# FMC_CONNECTOR.net
KiCad netlist of a schematic drawn in Altium Designer
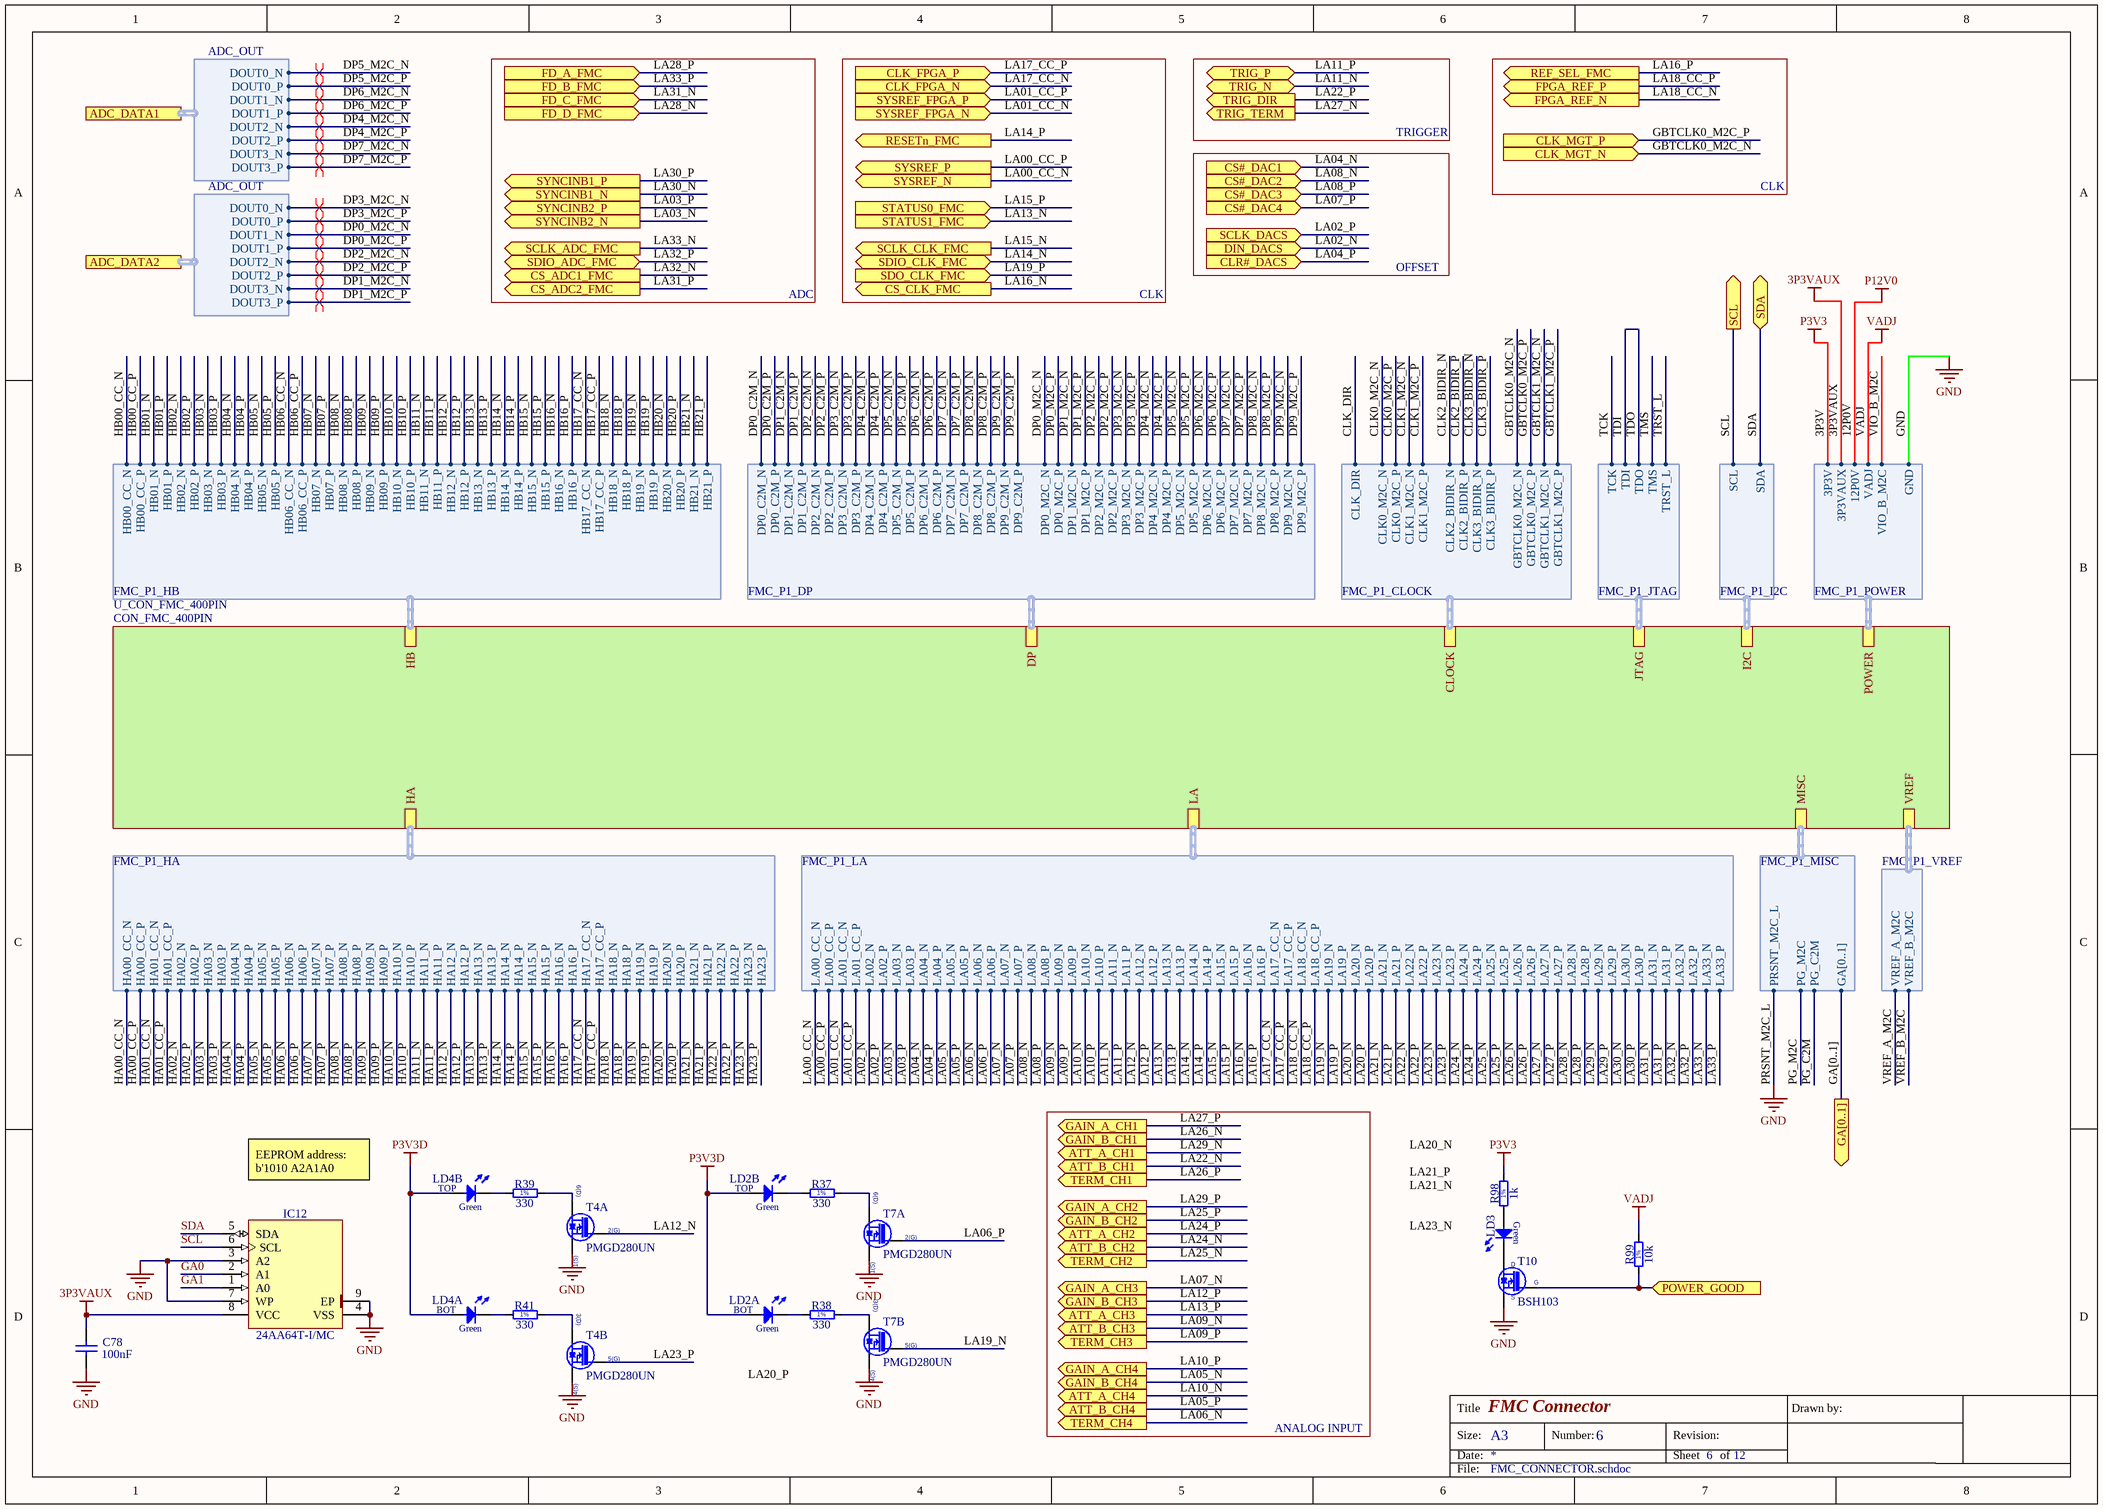
[diagram p0: FMC_CONNECTOR.schdoc]

(export (version "E")
  (design (tool "Eeschema 10.0.6"))
  (components
    (comp (ref "C78")
      (value "100nF")
      (footprint "CAPC0603X33N")
      (description "Non-polarised capacitor")
      (fields
        (field (name "TOLERANCE") "±10%")
        (field (name "PART NUMBER") "CC0201_100NF_6.3V_10%_X5R")
        (field (name "AUTHOR") "CERN DEM JLC")
      )
      (libsource (lib "Capacitors") (part "Capacitor - non polarized"))
    )
    (comp (ref "IC12")
      (value "24AA64T-I/MC")
      (footprint "SON50P300X200X100-9N-R175X155")
      (description "1.7V-5.5V 64K I2C Serial EEPROM")
      (fields (field (name "MANUFACTURER") "MICROCHIP TECHNOLOGY") (field (name "AUTHOR") "CERN DEM JLC"))
      (libsource (lib "ICs And Semiconductors") (part "24AA64T-I/MC"))
    )
    (comp (ref "LD2")
      (value "~")
      (footprint "553-xxxx-300")
      (description "LED x2 Green 553-0122-300")
      (fields
        (field (name "MANUFACTURER PART NUMBER") "553-0122-300")
        (field (name "MANUFACTURER") "Dialight")
      )
      (libsource (lib "FMC_ADC") (part "LED x2 Green 553-0122-300"))
    )
    (comp (ref "LD3")
      (value "~")
      (footprint "LED0603X65N")
      (description "LED Green, SMD 0603")
      (fields
        (field (name "MANUFACTURER PART NUMBER") "KPH-1608CGCK")
        (field (name "MANUFACTURER") "Kingbright")
      )
      (libsource (lib "FMC_ADC") (part "KPH-1608CGCK"))
    )
    (comp (ref "LD4")
      (value "~")
      (footprint "553-xxxx-300")
      (description "LED x2 Green 553-0122-300")
      (fields
        (field (name "MANUFACTURER PART NUMBER") "553-0122-300")
        (field (name "MANUFACTURER") "Dialight")
      )
      (libsource (lib "FMC_ADC") (part "LED x2 Green 553-0122-300"))
    )
    (comp (ref "R37")
      (value "330")
      (footprint "RESC1005X40N")
      (description "Resistor - 1%")
      (fields
        (field (name "PART NUMBER") "R0402_330R_1%_0.0625W_100PPM")
        (field (name "POWER") "0.0625W")
        (field (name "AUTHOR") "CERN DEM JLC")
      )
      (libsource (lib "Resistors") (part "Resistor - 1%"))
    )
    (comp (ref "R38")
      (value "330")
      (footprint "RESC1005X40N")
      (description "Resistor - 1%")
      (fields
        (field (name "PART NUMBER") "R0402_330R_1%_0.0625W_100PPM")
        (field (name "POWER") "0.0625W")
        (field (name "AUTHOR") "CERN DEM JLC")
      )
      (libsource (lib "Resistors") (part "Resistor - 1%"))
    )
    (comp (ref "R39")
      (value "330")
      (footprint "RESC1005X40N")
      (description "Resistor - 1%")
      (fields
        (field (name "PART NUMBER") "R0402_330R_1%_0.0625W_100PPM")
        (field (name "POWER") "0.0625W")
        (field (name "AUTHOR") "CERN DEM JLC")
      )
      (libsource (lib "Resistors") (part "Resistor - 1%"))
    )
    (comp (ref "R41")
      (value "330")
      (footprint "RESC1005X40N")
      (description "Resistor - 1%")
      (fields
        (field (name "PART NUMBER") "R0402_330R_1%_0.0625W_100PPM")
        (field (name "POWER") "0.0625W")
        (field (name "AUTHOR") "CERN DEM JLC")
      )
      (libsource (lib "Resistors") (part "Resistor - 1%"))
    )
    (comp (ref "R98")
      (value "1k")
      (footprint "RESC1005X40N")
      (description "Resistor - 1%")
      (fields
        (field (name "PART NUMBER") "R0402_1K_1%_0.0625W_100PPM")
        (field (name "POWER") "0.0625W")
        (field (name "AUTHOR") "CERN DEM JLC")
      )
      (libsource (lib "Resistors") (part "Resistor - 1%"))
    )
    (comp (ref "R99")
      (value "10k")
      (footprint "RESC1608X55N")
      (description "Resistor - 1%")
      (fields
        (field (name "PART NUMBER") "R0603_10K_1%_0.1W_100PPM")
        (field (name "POWER") "0.1W")
        (field (name "AUTHOR") "CERN DEM JLC")
      )
      (libsource (lib "Resistors") (part "Resistor - 1%"))
    )
    (comp (ref "T4")
      (value "PMGD280UN")
      (footprint "SOT65P210X110-6N")
      (description "Dual N-Channel micro TrenchMOS™ Ultra Low Level FET")
      (fields (field (name "MANUFACTURER") "NXP SEMICONDUCTORS") (field (name "AUTHOR") "CERN DEM JLC"))
      (libsource (lib "ICs And Semiconductors") (part "PMGD280UN"))
    )
    (comp (ref "T7")
      (value "PMGD280UN")
      (footprint "SOT65P210X110-6N")
      (description "Dual N-Channel micro TrenchMOS™ Ultra Low Level FET")
      (fields (field (name "MANUFACTURER") "NXP SEMICONDUCTORS") (field (name "AUTHOR") "CERN DEM JLC"))
      (libsource (lib "ICs And Semiconductors") (part "PMGD280UN"))
    )
    (comp (ref "T10")
      (value "BSH103")
      (footprint "SOT95P230X110-3N")
      (description "N-CHANNEL MOSFET WITH DIODE")
      (fields (field (name "MANUFACTURER") "NEXPERIA") (field (name "AUTHOR") "CERN DEM JLC"))
      (libsource (lib "ICs And Semiconductors") (part "N-MOSFET-D 1G 2S 3D"))
    )
  )
  (nets
    (net (code "61") (name "/GA0") (class "Default")
      (node (ref "IC12") (pin "2") (pinfunction "A1_2") (pintype "input"))
    )
    (net (code "62") (name "/GA1") (class "Default")
      (node (ref "IC12") (pin "1") (pinfunction "A0_1") (pintype "input"))
    )
    (net (code "173") (name "/LA06_P") (class "Default")
      (node (ref "T7") (pin "2") (pinfunction "G_2") (pintype "passive"))
    )
    (net (code "184") (name "/LA12_N") (class "Default")
      (node (ref "T4") (pin "2") (pinfunction "G_2") (pintype "passive"))
    )
    (net (code "198") (name "/LA19_N") (class "Default")
      (node (ref "T7") (pin "5") (pinfunction "G_5") (pintype "passive"))
    )
    (net (code "207") (name "/LA23_P") (class "Default")
      (node (ref "T4") (pin "5") (pinfunction "G_5") (pintype "passive"))
    )
    (net (code "230") (name "/POWER_GOOD") (class "Default")
      (node (ref "R99") (pin "1") (pinfunction "1_1") (pintype "passive"))
      (node (ref "T10") (pin "1") (pinfunction "G_1") (pintype "passive"))
    )
    (net (code "231") (name "/SCL") (class "Default")
      (node (ref "IC12") (pin "6") (pinfunction "SCL_6") (pintype "input"))
    )
    (net (code "232") (name "/SDA") (class "Default")
      (node (ref "IC12") (pin "5") (pinfunction "SDA_5") (pintype "bidirectional"))
    )
    (net (code "251") (name "3P3VAUX") (class "Default")
      (node (ref "C78") (pin "2") (pinfunction "2_2") (pintype "passive"))
      (node (ref "IC12") (pin "8") (pinfunction "VCC_8") (pintype "power_in"))
    )
    (net (code "252") (name "GND") (class "Default")
      (node (ref "C78") (pin "1") (pinfunction "1_1") (pintype "passive"))
      (node (ref "IC12") (pin "3") (pinfunction "A2_3") (pintype "input"))
      (node (ref "IC12") (pin "4") (pinfunction "VSS_4") (pintype "power_in"))
      (node (ref "IC12") (pin "7") (pinfunction "WP_7") (pintype "input"))
      (node (ref "IC12") (pin "9") (pinfunction "EP_9") (pintype "power_in"))
      (node (ref "T10") (pin "2") (pinfunction "S_2") (pintype "passive"))
      (node (ref "T4") (pin "1") (pinfunction "S_1") (pintype "passive"))
      (node (ref "T4") (pin "4") (pinfunction "S_4") (pintype "passive"))
      (node (ref "T7") (pin "1") (pinfunction "S_1") (pintype "passive"))
      (node (ref "T7") (pin "4") (pinfunction "S_4") (pintype "passive"))
    )
    (net (code "253") (name "Net-(LD2A-C)") (class "Default")
      (node (ref "LD2") (pin "1") (pinfunction "C_1") (pintype "passive"))
      (node (ref "R38") (pin "1") (pinfunction "1_1") (pintype "passive"))
    )
    (net (code "254") (name "Net-(LD2B-C)") (class "Default")
      (node (ref "LD2") (pin "3") (pinfunction "C_3") (pintype "passive"))
      (node (ref "R37") (pin "1") (pinfunction "1_1") (pintype "passive"))
    )
    (net (code "255") (name "Net-(LD3-A)") (class "Default")
      (node (ref "LD3") (pin "1") (pinfunction "A_1") (pintype "passive"))
      (node (ref "R98") (pin "1") (pinfunction "1_1") (pintype "passive"))
    )
    (net (code "256") (name "Net-(LD3-C)") (class "Default")
      (node (ref "LD3") (pin "2") (pinfunction "C_2") (pintype "passive"))
      (node (ref "T10") (pin "3") (pinfunction "D_3") (pintype "passive"))
    )
    (net (code "257") (name "Net-(LD4A-C)") (class "Default")
      (node (ref "LD4") (pin "1") (pinfunction "C_1") (pintype "passive"))
      (node (ref "R41") (pin "1") (pinfunction "1_1") (pintype "passive"))
    )
    (net (code "258") (name "Net-(LD4B-C)") (class "Default")
      (node (ref "LD4") (pin "3") (pinfunction "C_3") (pintype "passive"))
      (node (ref "R39") (pin "1") (pinfunction "1_1") (pintype "passive"))
    )
    (net (code "259") (name "Net-(T4A-D)") (class "Default")
      (node (ref "R39") (pin "2") (pinfunction "2_2") (pintype "passive"))
      (node (ref "T4") (pin "6") (pinfunction "D_6") (pintype "passive"))
    )
    (net (code "260") (name "Net-(T4B-D)") (class "Default")
      (node (ref "R41") (pin "2") (pinfunction "2_2") (pintype "passive"))
      (node (ref "T4") (pin "3") (pinfunction "D_3") (pintype "passive"))
    )
    (net (code "261") (name "Net-(T7A-D)") (class "Default")
      (node (ref "R37") (pin "2") (pinfunction "2_2") (pintype "passive"))
      (node (ref "T7") (pin "6") (pinfunction "D_6") (pintype "passive"))
    )
    (net (code "262") (name "Net-(T7B-D)") (class "Default")
      (node (ref "R38") (pin "2") (pinfunction "2_2") (pintype "passive"))
      (node (ref "T7") (pin "3") (pinfunction "D_3") (pintype "passive"))
    )
    (net (code "263") (name "P3V3") (class "Default")
      (node (ref "R98") (pin "2") (pinfunction "2_2") (pintype "passive"))
    )
    (net (code "264") (name "P3V3D") (class "Default")
      (node (ref "LD2") (pin "2") (pinfunction "A_2") (pintype "passive"))
      (node (ref "LD2") (pin "4") (pinfunction "A_4") (pintype "passive"))
      (node (ref "LD4") (pin "2") (pinfunction "A_2") (pintype "passive"))
      (node (ref "LD4") (pin "4") (pinfunction "A_4") (pintype "passive"))
    )
    (net (code "266") (name "VADJ") (class "Default")
      (node (ref "R99") (pin "2") (pinfunction "2_2") (pintype "passive"))
    )
  )
)
